# Brainc.net
KiCad netlist of a schematic drawn in EAGLE
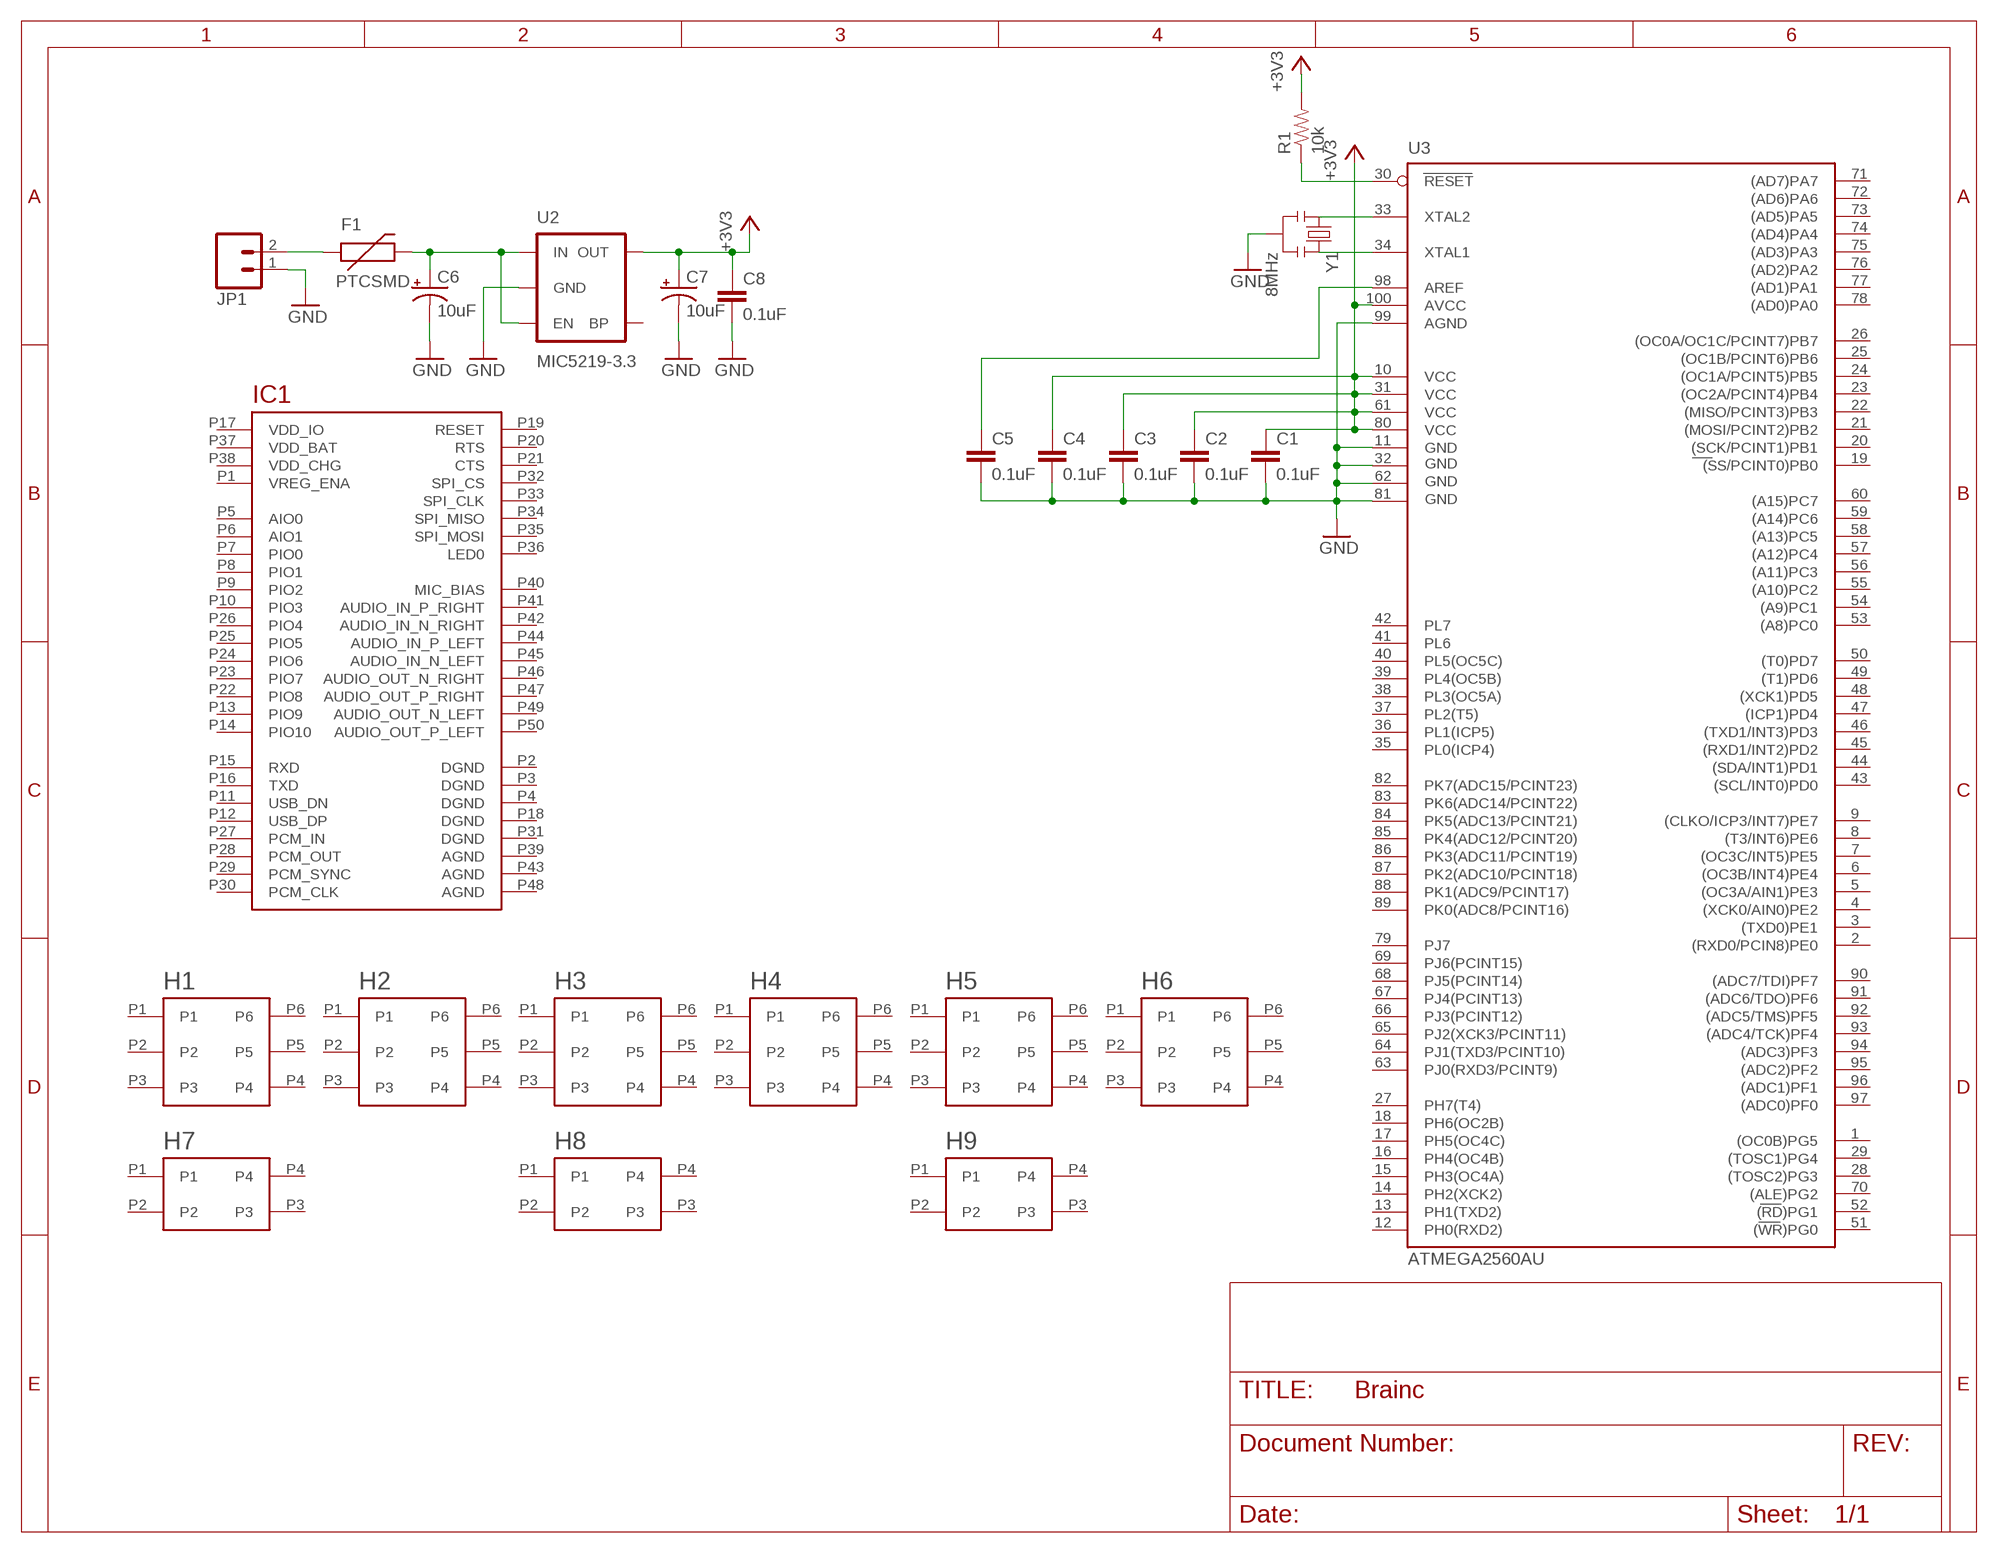
[diagram p0: schematic, sheet 1]

(export (version "E")
  (design (tool "Eeschema 10.0.6"))
  (components
    (comp (ref "C1")
      (value "0.1uF")
      (footprint "eagle-import:0603-CAP")
      (libsource (lib "eagle-import") (part "CAP0603-CAP"))
    )
    (comp (ref "C2")
      (value "0.1uF")
      (footprint "eagle-import:0603-CAP")
      (libsource (lib "eagle-import") (part "CAP0603-CAP"))
    )
    (comp (ref "C3")
      (value "0.1uF")
      (footprint "eagle-import:0603-CAP")
      (libsource (lib "eagle-import") (part "CAP0603-CAP"))
    )
    (comp (ref "C4")
      (value "0.1uF")
      (footprint "eagle-import:0603-CAP")
      (libsource (lib "eagle-import") (part "CAP0603-CAP"))
    )
    (comp (ref "C5")
      (value "0.1uF")
      (footprint "eagle-import:0603-CAP")
      (libsource (lib "eagle-import") (part "CAP0603-CAP"))
    )
    (comp (ref "C6")
      (value "10uF")
      (footprint "eagle-import:EIA3216")
      (libsource (lib "eagle-import") (part "CAP_POL1206"))
    )
    (comp (ref "C7")
      (value "10uF")
      (footprint "eagle-import:EIA3216")
      (libsource (lib "eagle-import") (part "CAP_POL1206"))
    )
    (comp (ref "C8")
      (value "0.1uF")
      (footprint "eagle-import:0603-CAP")
      (libsource (lib "eagle-import") (part "CAP0603-CAP"))
    )
    (comp (ref "F1")
      (value "PTCSMD")
      (footprint "eagle-import:PTC-1206")
      (libsource (lib "eagle-import") (part "PTCSMD"))
    )
    (comp (ref "H1")
      (value "3X2F_1MM_SMD")
      (footprint "eagle-import:3X2F_1MM_SMD")
      (libsource (lib "eagle-import") (part "3X2F_1MM_SMD"))
    )
    (comp (ref "H2")
      (value "3X2F_1MM_SMD")
      (footprint "eagle-import:3X2F_1MM_SMD")
      (libsource (lib "eagle-import") (part "3X2F_1MM_SMD"))
    )
    (comp (ref "H3")
      (value "3X2F_1MM_SMD")
      (footprint "eagle-import:3X2F_1MM_SMD")
      (libsource (lib "eagle-import") (part "3X2F_1MM_SMD"))
    )
    (comp (ref "H4")
      (value "3X2F_1MM_SMD")
      (footprint "eagle-import:3X2F_1MM_SMD")
      (libsource (lib "eagle-import") (part "3X2F_1MM_SMD"))
    )
    (comp (ref "H5")
      (value "3X2F_1MM_SMD")
      (footprint "eagle-import:3X2F_1MM_SMD")
      (libsource (lib "eagle-import") (part "3X2F_1MM_SMD"))
    )
    (comp (ref "H6")
      (value "3X2F_1MM_SMD")
      (footprint "eagle-import:3X2F_1MM_SMD")
      (libsource (lib "eagle-import") (part "3X2F_1MM_SMD"))
    )
    (comp (ref "H7")
      (value "2X2F_1MM_SMD")
      (footprint "eagle-import:2X2F_1MM_SMD")
      (libsource (lib "eagle-import") (part "2X2F_1MM_SMD"))
    )
    (comp (ref "H8")
      (value "2X2F_1MM_SMD")
      (footprint "eagle-import:2X2F_1MM_SMD")
      (libsource (lib "eagle-import") (part "2X2F_1MM_SMD"))
    )
    (comp (ref "H9")
      (value "2X2F_1MM_SMD")
      (footprint "eagle-import:2X2F_1MM_SMD")
      (libsource (lib "eagle-import") (part "2X2F_1MM_SMD"))
    )
    (comp (ref "IC1")
      (value "WT32WT32")
      (footprint "eagle-import:WT32")
      (libsource (lib "eagle-import") (part "WT32WT32"))
    )
    (comp (ref "JP1")
      (value "M02-JST-2MM-SMT")
      (footprint "eagle-import:JST-2-SMD")
      (libsource (lib "eagle-import") (part "M02-JST-2MM-SMT"))
    )
    (comp (ref "R1")
      (value "10k")
      (footprint "eagle-import:0603-RES")
      (libsource (lib "eagle-import") (part "RESISTOR0603-RES"))
    )
    (comp (ref "U2")
      (value "MIC5219-3.3")
      (footprint "eagle-import:SOT23-5")
      (libsource (lib "eagle-import") (part "V_REG_MIC5219SMD"))
    )
    (comp (ref "U3")
      (value "ATMEGA2560AU")
      (footprint "eagle-import:TQFP100")
      (libsource (lib "eagle-import") (part "ATMEGA2560AU"))
    )
    (comp (ref "Y1")
      (value "8MHz")
      (footprint "eagle-import:RESONATOR-SMD")
      (libsource (lib "eagle-import") (part "RESONATORSMD"))
    )
  )
  (nets
    (net (code "1") (name "+3V3") (class "Default")
      (node (ref "C1") (pin "1") (pinfunction "1_1") (pintype "passive"))
      (node (ref "C2") (pin "1") (pinfunction "1_1") (pintype "passive"))
      (node (ref "C3") (pin "1") (pinfunction "1_1") (pintype "passive"))
      (node (ref "C4") (pin "1") (pinfunction "1_1") (pintype "passive"))
      (node (ref "C7") (pin "A") (pinfunction "+_A") (pintype "passive"))
      (node (ref "C8") (pin "1") (pinfunction "1_1") (pintype "passive"))
      (node (ref "R1") (pin "2") (pinfunction "2_2") (pintype "passive"))
      (node (ref "U2") (pin "5") (pinfunction "OUT_5") (pintype "passive"))
      (node (ref "U3") (pin "10") (pinfunction "VCC_10") (pintype "power_in"))
      (node (ref "U3") (pin "100") (pinfunction "AVCC_100") (pintype "power_in"))
      (node (ref "U3") (pin "31") (pinfunction "VCC1_31") (pintype "power_in"))
      (node (ref "U3") (pin "61") (pinfunction "VCC2_61") (pintype "power_in"))
      (node (ref "U3") (pin "80") (pinfunction "VCC3_80") (pintype "power_in"))
    )
    (net (code "2") (name "GND") (class "Default")
      (node (ref "C1") (pin "2") (pinfunction "2_2") (pintype "passive"))
      (node (ref "C2") (pin "2") (pinfunction "2_2") (pintype "passive"))
      (node (ref "C3") (pin "2") (pinfunction "2_2") (pintype "passive"))
      (node (ref "C4") (pin "2") (pinfunction "2_2") (pintype "passive"))
      (node (ref "C5") (pin "2") (pinfunction "2_2") (pintype "passive"))
      (node (ref "C6") (pin "C") (pinfunction "-_C") (pintype "passive"))
      (node (ref "C7") (pin "C") (pinfunction "-_C") (pintype "passive"))
      (node (ref "C8") (pin "2") (pinfunction "2_2") (pintype "passive"))
      (node (ref "JP1") (pin "1") (pinfunction "2_1") (pintype "passive"))
      (node (ref "U2") (pin "2") (pinfunction "GND_2") (pintype "input"))
      (node (ref "U3") (pin "11") (pinfunction "GND_11") (pintype "power_in"))
      (node (ref "U3") (pin "32") (pinfunction "GND1_32") (pintype "power_in"))
      (node (ref "U3") (pin "62") (pinfunction "GND2_62") (pintype "power_in"))
      (node (ref "U3") (pin "81") (pinfunction "GND3_81") (pintype "power_in"))
      (node (ref "U3") (pin "99") (pinfunction "AGND_99") (pintype "power_in"))
      (node (ref "Y1") (pin "2") (pinfunction "2_2") (pintype "passive"))
    )
    (net (code "3") (name "Net-(C6-+)") (class "Default")
      (node (ref "C6") (pin "A") (pinfunction "+_A") (pintype "passive"))
      (node (ref "F1") (pin "2") (pinfunction "2_2") (pintype "bidirectional"))
      (node (ref "U2") (pin "1") (pinfunction "IN_1") (pintype "input"))
      (node (ref "U2") (pin "3") (pinfunction "EN_3") (pintype "input"))
    )
    (net (code "4") (name "Net-(JP1-1)") (class "Default")
      (node (ref "F1") (pin "1") (pinfunction "1_1") (pintype "bidirectional"))
      (node (ref "JP1") (pin "2") (pinfunction "1_2") (pintype "passive"))
    )
    (net (code "5") (name "Net-(U3-AREF)") (class "Default")
      (node (ref "C5") (pin "1") (pinfunction "1_1") (pintype "passive"))
      (node (ref "U3") (pin "98") (pinfunction "AREF_98") (pintype "bidirectional"))
    )
    (net (code "6") (name "Net-(U3-RESET)") (class "Default")
      (node (ref "R1") (pin "1") (pinfunction "1_1") (pintype "passive"))
      (node (ref "U3") (pin "30") (pinfunction "RESET_30") (pintype "input"))
    )
    (net (code "7") (name "Net-(U3-XTAL1)") (class "Default")
      (node (ref "U3") (pin "34") (pinfunction "XTAL1_34") (pintype "input"))
      (node (ref "Y1") (pin "3") (pinfunction "3_3") (pintype "passive"))
    )
    (net (code "8") (name "Net-(U3-XTAL2)") (class "Default")
      (node (ref "U3") (pin "33") (pinfunction "XTAL2_33") (pintype "output"))
      (node (ref "Y1") (pin "1") (pinfunction "1_1") (pintype "passive"))
    )
    (net (code "9") (name "unconnected-(H1-PadP1)") (class "Default")
      (node (ref "H1") (pin "P1") (pinfunction "P1_P1") (pintype "bidirectional"))
    )
    (net (code "10") (name "unconnected-(H1-PadP2)") (class "Default")
      (node (ref "H1") (pin "P2") (pinfunction "P2_P2") (pintype "bidirectional"))
    )
    (net (code "11") (name "unconnected-(H1-PadP3)") (class "Default")
      (node (ref "H1") (pin "P3") (pinfunction "P3_P3") (pintype "bidirectional"))
    )
    (net (code "12") (name "unconnected-(H1-PadP4)") (class "Default")
      (node (ref "H1") (pin "P4") (pinfunction "P4_P4") (pintype "bidirectional"))
    )
    (net (code "13") (name "unconnected-(H1-PadP5)") (class "Default")
      (node (ref "H1") (pin "P5") (pinfunction "P5_P5") (pintype "bidirectional"))
    )
    (net (code "14") (name "unconnected-(H1-PadP6)") (class "Default")
      (node (ref "H1") (pin "P6") (pinfunction "P6_P6") (pintype "bidirectional"))
    )
    (net (code "15") (name "unconnected-(H2-PadP1)") (class "Default")
      (node (ref "H2") (pin "P1") (pinfunction "P1_P1") (pintype "bidirectional"))
    )
    (net (code "16") (name "unconnected-(H2-PadP2)") (class "Default")
      (node (ref "H2") (pin "P2") (pinfunction "P2_P2") (pintype "bidirectional"))
    )
    (net (code "17") (name "unconnected-(H2-PadP3)") (class "Default")
      (node (ref "H2") (pin "P3") (pinfunction "P3_P3") (pintype "bidirectional"))
    )
    (net (code "18") (name "unconnected-(H2-PadP4)") (class "Default")
      (node (ref "H2") (pin "P4") (pinfunction "P4_P4") (pintype "bidirectional"))
    )
    (net (code "19") (name "unconnected-(H2-PadP5)") (class "Default")
      (node (ref "H2") (pin "P5") (pinfunction "P5_P5") (pintype "bidirectional"))
    )
    (net (code "20") (name "unconnected-(H2-PadP6)") (class "Default")
      (node (ref "H2") (pin "P6") (pinfunction "P6_P6") (pintype "bidirectional"))
    )
    (net (code "21") (name "unconnected-(H3-PadP1)") (class "Default")
      (node (ref "H3") (pin "P1") (pinfunction "P1_P1") (pintype "bidirectional"))
    )
    (net (code "22") (name "unconnected-(H3-PadP2)") (class "Default")
      (node (ref "H3") (pin "P2") (pinfunction "P2_P2") (pintype "bidirectional"))
    )
    (net (code "23") (name "unconnected-(H3-PadP3)") (class "Default")
      (node (ref "H3") (pin "P3") (pinfunction "P3_P3") (pintype "bidirectional"))
    )
    (net (code "24") (name "unconnected-(H3-PadP4)") (class "Default")
      (node (ref "H3") (pin "P4") (pinfunction "P4_P4") (pintype "bidirectional"))
    )
    (net (code "25") (name "unconnected-(H3-PadP5)") (class "Default")
      (node (ref "H3") (pin "P5") (pinfunction "P5_P5") (pintype "bidirectional"))
    )
    (net (code "26") (name "unconnected-(H3-PadP6)") (class "Default")
      (node (ref "H3") (pin "P6") (pinfunction "P6_P6") (pintype "bidirectional"))
    )
    (net (code "27") (name "unconnected-(H4-PadP1)") (class "Default")
      (node (ref "H4") (pin "P1") (pinfunction "P1_P1") (pintype "bidirectional"))
    )
    (net (code "28") (name "unconnected-(H4-PadP2)") (class "Default")
      (node (ref "H4") (pin "P2") (pinfunction "P2_P2") (pintype "bidirectional"))
    )
    (net (code "29") (name "unconnected-(H4-PadP3)") (class "Default")
      (node (ref "H4") (pin "P3") (pinfunction "P3_P3") (pintype "bidirectional"))
    )
    (net (code "30") (name "unconnected-(H4-PadP4)") (class "Default")
      (node (ref "H4") (pin "P4") (pinfunction "P4_P4") (pintype "bidirectional"))
    )
    (net (code "31") (name "unconnected-(H4-PadP5)") (class "Default")
      (node (ref "H4") (pin "P5") (pinfunction "P5_P5") (pintype "bidirectional"))
    )
    (net (code "32") (name "unconnected-(H4-PadP6)") (class "Default")
      (node (ref "H4") (pin "P6") (pinfunction "P6_P6") (pintype "bidirectional"))
    )
    (net (code "33") (name "unconnected-(H5-PadP1)") (class "Default")
      (node (ref "H5") (pin "P1") (pinfunction "P1_P1") (pintype "bidirectional"))
    )
    (net (code "34") (name "unconnected-(H5-PadP2)") (class "Default")
      (node (ref "H5") (pin "P2") (pinfunction "P2_P2") (pintype "bidirectional"))
    )
    (net (code "35") (name "unconnected-(H5-PadP3)") (class "Default")
      (node (ref "H5") (pin "P3") (pinfunction "P3_P3") (pintype "bidirectional"))
    )
    (net (code "36") (name "unconnected-(H5-PadP4)") (class "Default")
      (node (ref "H5") (pin "P4") (pinfunction "P4_P4") (pintype "bidirectional"))
    )
    (net (code "37") (name "unconnected-(H5-PadP5)") (class "Default")
      (node (ref "H5") (pin "P5") (pinfunction "P5_P5") (pintype "bidirectional"))
    )
    (net (code "38") (name "unconnected-(H5-PadP6)") (class "Default")
      (node (ref "H5") (pin "P6") (pinfunction "P6_P6") (pintype "bidirectional"))
    )
    (net (code "39") (name "unconnected-(H6-PadP1)") (class "Default")
      (node (ref "H6") (pin "P1") (pinfunction "P1_P1") (pintype "bidirectional"))
    )
    (net (code "40") (name "unconnected-(H6-PadP2)") (class "Default")
      (node (ref "H6") (pin "P2") (pinfunction "P2_P2") (pintype "bidirectional"))
    )
    (net (code "41") (name "unconnected-(H6-PadP3)") (class "Default")
      (node (ref "H6") (pin "P3") (pinfunction "P3_P3") (pintype "bidirectional"))
    )
    (net (code "42") (name "unconnected-(H6-PadP4)") (class "Default")
      (node (ref "H6") (pin "P4") (pinfunction "P4_P4") (pintype "bidirectional"))
    )
    (net (code "43") (name "unconnected-(H6-PadP5)") (class "Default")
      (node (ref "H6") (pin "P5") (pinfunction "P5_P5") (pintype "bidirectional"))
    )
    (net (code "44") (name "unconnected-(H6-PadP6)") (class "Default")
      (node (ref "H6") (pin "P6") (pinfunction "P6_P6") (pintype "bidirectional"))
    )
    (net (code "45") (name "unconnected-(H7-PadP1)") (class "Default")
      (node (ref "H7") (pin "P1") (pinfunction "P1_P1") (pintype "bidirectional"))
    )
    (net (code "46") (name "unconnected-(H7-PadP2)") (class "Default")
      (node (ref "H7") (pin "P2") (pinfunction "P2_P2") (pintype "bidirectional"))
    )
    (net (code "47") (name "unconnected-(H7-PadP3)") (class "Default")
      (node (ref "H7") (pin "P3") (pinfunction "P3_P3") (pintype "bidirectional"))
    )
    (net (code "48") (name "unconnected-(H7-PadP4)") (class "Default")
      (node (ref "H7") (pin "P4") (pinfunction "P4_P4") (pintype "bidirectional"))
    )
    (net (code "49") (name "unconnected-(H8-PadP1)") (class "Default")
      (node (ref "H8") (pin "P1") (pinfunction "P1_P1") (pintype "bidirectional"))
    )
    (net (code "50") (name "unconnected-(H8-PadP2)") (class "Default")
      (node (ref "H8") (pin "P2") (pinfunction "P2_P2") (pintype "bidirectional"))
    )
    (net (code "51") (name "unconnected-(H8-PadP3)") (class "Default")
      (node (ref "H8") (pin "P3") (pinfunction "P3_P3") (pintype "bidirectional"))
    )
    (net (code "52") (name "unconnected-(H8-PadP4)") (class "Default")
      (node (ref "H8") (pin "P4") (pinfunction "P4_P4") (pintype "bidirectional"))
    )
    (net (code "53") (name "unconnected-(H9-PadP1)") (class "Default")
      (node (ref "H9") (pin "P1") (pinfunction "P1_P1") (pintype "bidirectional"))
    )
    (net (code "54") (name "unconnected-(H9-PadP2)") (class "Default")
      (node (ref "H9") (pin "P2") (pinfunction "P2_P2") (pintype "bidirectional"))
    )
    (net (code "55") (name "unconnected-(H9-PadP3)") (class "Default")
      (node (ref "H9") (pin "P3") (pinfunction "P3_P3") (pintype "bidirectional"))
    )
    (net (code "56") (name "unconnected-(H9-PadP4)") (class "Default")
      (node (ref "H9") (pin "P4") (pinfunction "P4_P4") (pintype "bidirectional"))
    )
    (net (code "57") (name "unconnected-(IC1-AGND-PadP39)") (class "Default")
      (node (ref "IC1") (pin "P39") (pinfunction "AGND_P39") (pintype "bidirectional"))
    )
    (net (code "58") (name "unconnected-(IC1-AGND-PadP43)") (class "Default")
      (node (ref "IC1") (pin "P43") (pinfunction "AGND_P43") (pintype "bidirectional"))
    )
    (net (code "59") (name "unconnected-(IC1-AGND-PadP48)") (class "Default")
      (node (ref "IC1") (pin "P48") (pinfunction "AGND_P48") (pintype "bidirectional"))
    )
    (net (code "60") (name "unconnected-(IC1-AIO0-PadP5)") (class "Default")
      (node (ref "IC1") (pin "P5") (pinfunction "AIO0_P5") (pintype "bidirectional"))
    )
    (net (code "61") (name "unconnected-(IC1-AIO1-PadP6)") (class "Default")
      (node (ref "IC1") (pin "P6") (pinfunction "AIO1_P6") (pintype "bidirectional"))
    )
    (net (code "62") (name "unconnected-(IC1-AUDIO_IN_N_LEFT-PadP45)") (class "Default")
      (node (ref "IC1") (pin "P45") (pinfunction "AUDIO_IN_N_LEFT_P45") (pintype "bidirectional"))
    )
    (net (code "63") (name "unconnected-(IC1-AUDIO_IN_N_RIGHT-PadP42)") (class "Default")
      (node (ref "IC1") (pin "P42") (pinfunction "AUDIO_IN_N_RIGHT_P42") (pintype "bidirectional"))
    )
    (net (code "64") (name "unconnected-(IC1-AUDIO_IN_P_LEFT-PadP44)") (class "Default")
      (node (ref "IC1") (pin "P44") (pinfunction "AUDIO_IN_P_LEFT_P44") (pintype "bidirectional"))
    )
    (net (code "65") (name "unconnected-(IC1-AUDIO_IN_P_RIGHT-PadP41)") (class "Default")
      (node (ref "IC1") (pin "P41") (pinfunction "AUDIO_IN_P_RIGHT_P41") (pintype "bidirectional"))
    )
    (net (code "66") (name "unconnected-(IC1-AUDIO_OUT_N_LEFT-PadP49)") (class "Default")
      (node (ref "IC1") (pin "P49") (pinfunction "AUDIO_OUT_N_LEFT_P49") (pintype "bidirectional"))
    )
    (net (code "67") (name "unconnected-(IC1-AUDIO_OUT_N_RIGHT-PadP46)") (class "Default")
      (node (ref "IC1") (pin "P46") (pinfunction "AUDIO_OUT_N_RIGHT_P46") (pintype "bidirectional"))
    )
    (net (code "68") (name "unconnected-(IC1-AUDIO_OUT_P_LEFT-PadP50)") (class "Default")
      (node (ref "IC1") (pin "P50") (pinfunction "AUDIO_OUT_P_LEFT_P50") (pintype "bidirectional"))
    )
    (net (code "69") (name "unconnected-(IC1-AUDIO_OUT_P_RIGHT-PadP47)") (class "Default")
      (node (ref "IC1") (pin "P47") (pinfunction "AUDIO_OUT_P_RIGHT_P47") (pintype "bidirectional"))
    )
    (net (code "70") (name "unconnected-(IC1-CTS-PadP21)") (class "Default")
      (node (ref "IC1") (pin "P21") (pinfunction "CTS_P21") (pintype "bidirectional"))
    )
    (net (code "71") (name "unconnected-(IC1-DGND-PadP2)") (class "Default")
      (node (ref "IC1") (pin "P2") (pinfunction "DGND_P2") (pintype "bidirectional"))
    )
    (net (code "72") (name "unconnected-(IC1-DGND-PadP3)") (class "Default")
      (node (ref "IC1") (pin "P3") (pinfunction "DGND_P3") (pintype "bidirectional"))
    )
    (net (code "73") (name "unconnected-(IC1-DGND-PadP4)") (class "Default")
      (node (ref "IC1") (pin "P4") (pinfunction "DGND_P4") (pintype "bidirectional"))
    )
    (net (code "74") (name "unconnected-(IC1-DGND-PadP18)") (class "Default")
      (node (ref "IC1") (pin "P18") (pinfunction "DGND_P18") (pintype "bidirectional"))
    )
    (net (code "75") (name "unconnected-(IC1-DGND-PadP31)") (class "Default")
      (node (ref "IC1") (pin "P31") (pinfunction "DGND_P31") (pintype "bidirectional"))
    )
    (net (code "76") (name "unconnected-(IC1-LED0-PadP36)") (class "Default")
      (node (ref "IC1") (pin "P36") (pinfunction "LED0_P36") (pintype "bidirectional"))
    )
    (net (code "77") (name "unconnected-(IC1-MIC_BIAS-PadP40)") (class "Default")
      (node (ref "IC1") (pin "P40") (pinfunction "MIC_BIAS_P40") (pintype "bidirectional"))
    )
    (net (code "78") (name "unconnected-(IC1-PCM_CLK-PadP30)") (class "Default")
      (node (ref "IC1") (pin "P30") (pinfunction "PCM_CLK_P30") (pintype "bidirectional"))
    )
    (net (code "79") (name "unconnected-(IC1-PCM_IN-PadP27)") (class "Default")
      (node (ref "IC1") (pin "P27") (pinfunction "PCM_IN_P27") (pintype "bidirectional"))
    )
    (net (code "80") (name "unconnected-(IC1-PCM_OUT-PadP28)") (class "Default")
      (node (ref "IC1") (pin "P28") (pinfunction "PCM_OUT_P28") (pintype "bidirectional"))
    )
    (net (code "81") (name "unconnected-(IC1-PCM_SYNC-PadP29)") (class "Default")
      (node (ref "IC1") (pin "P29") (pinfunction "PCM_SYNC_P29") (pintype "bidirectional"))
    )
    (net (code "82") (name "unconnected-(IC1-PIO0-PadP7)") (class "Default")
      (node (ref "IC1") (pin "P7") (pinfunction "PIO0_P7") (pintype "bidirectional"))
    )
    (net (code "83") (name "unconnected-(IC1-PIO1-PadP8)") (class "Default")
      (node (ref "IC1") (pin "P8") (pinfunction "PIO1_P8") (pintype "bidirectional"))
    )
    (net (code "84") (name "unconnected-(IC1-PIO2-PadP9)") (class "Default")
      (node (ref "IC1") (pin "P9") (pinfunction "PIO2_P9") (pintype "bidirectional"))
    )
    (net (code "85") (name "unconnected-(IC1-PIO3-PadP10)") (class "Default")
      (node (ref "IC1") (pin "P10") (pinfunction "PIO3_P10") (pintype "bidirectional"))
    )
    (net (code "86") (name "unconnected-(IC1-PIO4-PadP26)") (class "Default")
      (node (ref "IC1") (pin "P26") (pinfunction "PIO4_P26") (pintype "bidirectional"))
    )
    (net (code "87") (name "unconnected-(IC1-PIO5-PadP25)") (class "Default")
      (node (ref "IC1") (pin "P25") (pinfunction "PIO5_P25") (pintype "bidirectional"))
    )
    (net (code "88") (name "unconnected-(IC1-PIO6-PadP24)") (class "Default")
      (node (ref "IC1") (pin "P24") (pinfunction "PIO6_P24") (pintype "bidirectional"))
    )
    (net (code "89") (name "unconnected-(IC1-PIO7-PadP23)") (class "Default")
      (node (ref "IC1") (pin "P23") (pinfunction "PIO7_P23") (pintype "bidirectional"))
    )
    (net (code "90") (name "unconnected-(IC1-PIO8-PadP22)") (class "Default")
      (node (ref "IC1") (pin "P22") (pinfunction "PIO8_P22") (pintype "bidirectional"))
    )
    (net (code "91") (name "unconnected-(IC1-PIO9-PadP13)") (class "Default")
      (node (ref "IC1") (pin "P13") (pinfunction "PIO9_P13") (pintype "bidirectional"))
    )
    (net (code "92") (name "unconnected-(IC1-PIO10-PadP14)") (class "Default")
      (node (ref "IC1") (pin "P14") (pinfunction "PIO10_P14") (pintype "bidirectional"))
    )
    (net (code "93") (name "unconnected-(IC1-RESET-PadP19)") (class "Default")
      (node (ref "IC1") (pin "P19") (pinfunction "RESET_P19") (pintype "bidirectional"))
    )
    (net (code "94") (name "unconnected-(IC1-RTS-PadP20)") (class "Default")
      (node (ref "IC1") (pin "P20") (pinfunction "RTS_P20") (pintype "bidirectional"))
    )
    (net (code "95") (name "unconnected-(IC1-RXD-PadP15)") (class "Default")
      (node (ref "IC1") (pin "P15") (pinfunction "RXD_P15") (pintype "bidirectional"))
    )
    (net (code "96") (name "unconnected-(IC1-SPI_CLK-PadP33)") (class "Default")
      (node (ref "IC1") (pin "P33") (pinfunction "SPI_CLK_P33") (pintype "bidirectional"))
    )
    (net (code "97") (name "unconnected-(IC1-SPI_CS-PadP32)") (class "Default")
      (node (ref "IC1") (pin "P32") (pinfunction "SPI_CS_P32") (pintype "bidirectional"))
    )
    (net (code "98") (name "unconnected-(IC1-SPI_MISO-PadP34)") (class "Default")
      (node (ref "IC1") (pin "P34") (pinfunction "SPI_MISO_P34") (pintype "bidirectional"))
    )
    (net (code "99") (name "unconnected-(IC1-SPI_MOSI-PadP35)") (class "Default")
      (node (ref "IC1") (pin "P35") (pinfunction "SPI_MOSI_P35") (pintype "bidirectional"))
    )
    (net (code "100") (name "unconnected-(IC1-TXD-PadP16)") (class "Default")
      (node (ref "IC1") (pin "P16") (pinfunction "TXD_P16") (pintype "bidirectional"))
    )
    (net (code "101") (name "unconnected-(IC1-USB_DN-PadP11)") (class "Default")
      (node (ref "IC1") (pin "P11") (pinfunction "USB_DN_P11") (pintype "bidirectional"))
    )
    (net (code "102") (name "unconnected-(IC1-USB_DP-PadP12)") (class "Default")
      (node (ref "IC1") (pin "P12") (pinfunction "USB_DP_P12") (pintype "bidirectional"))
    )
    (net (code "103") (name "unconnected-(IC1-VDD_BAT-PadP37)") (class "Default")
      (node (ref "IC1") (pin "P37") (pinfunction "VDD_BAT_P37") (pintype "bidirectional"))
    )
    (net (code "104") (name "unconnected-(IC1-VDD_CHG-PadP38)") (class "Default")
      (node (ref "IC1") (pin "P38") (pinfunction "VDD_CHG_P38") (pintype "bidirectional"))
    )
    (net (code "105") (name "unconnected-(IC1-VDD_IO-PadP17)") (class "Default")
      (node (ref "IC1") (pin "P17") (pinfunction "VDD_IO_P17") (pintype "bidirectional"))
    )
    (net (code "106") (name "unconnected-(IC1-VREG_ENA-PadP1)") (class "Default")
      (node (ref "IC1") (pin "P1") (pinfunction "VREG_ENA_P1") (pintype "bidirectional"))
    )
    (net (code "107") (name "unconnected-(U2-BP-Pad4)") (class "Default")
      (node (ref "U2") (pin "4") (pinfunction "BP_4") (pintype "input"))
    )
    (net (code "108") (name "unconnected-(U3-(A8)PC0-Pad53)") (class "Default")
      (node (ref "U3") (pin "53") (pinfunction "(A8)PC0_53") (pintype "bidirectional"))
    )
    (net (code "109") (name "unconnected-(U3-(A9)PC1-Pad54)") (class "Default")
      (node (ref "U3") (pin "54") (pinfunction "(A9)PC1_54") (pintype "bidirectional"))
    )
    (net (code "110") (name "unconnected-(U3-(A10)PC2-Pad55)") (class "Default")
      (node (ref "U3") (pin "55") (pinfunction "(A10)PC2_55") (pintype "bidirectional"))
    )
    (net (code "111") (name "unconnected-(U3-(A11)PC3-Pad56)") (class "Default")
      (node (ref "U3") (pin "56") (pinfunction "(A11)PC3_56") (pintype "bidirectional"))
    )
    (net (code "112") (name "unconnected-(U3-(A12)PC4-Pad57)") (class "Default")
      (node (ref "U3") (pin "57") (pinfunction "(A12)PC4_57") (pintype "bidirectional"))
    )
    (net (code "113") (name "unconnected-(U3-(A13)PC5-Pad58)") (class "Default")
      (node (ref "U3") (pin "58") (pinfunction "(A13)PC5_58") (pintype "bidirectional"))
    )
    (net (code "114") (name "unconnected-(U3-(A14)PC6-Pad59)") (class "Default")
      (node (ref "U3") (pin "59") (pinfunction "(A14)PC6_59") (pintype "bidirectional"))
    )
    (net (code "115") (name "unconnected-(U3-(A15)PC7-Pad60)") (class "Default")
      (node (ref "U3") (pin "60") (pinfunction "(A15)PC7_60") (pintype "bidirectional"))
    )
    (net (code "116") (name "unconnected-(U3-(AD0)PA0-Pad78)") (class "Default")
      (node (ref "U3") (pin "78") (pinfunction "(AD0)PA0_78") (pintype "bidirectional"))
    )
    (net (code "117") (name "unconnected-(U3-(AD1)PA1-Pad77)") (class "Default")
      (node (ref "U3") (pin "77") (pinfunction "(AD1)PA1_77") (pintype "bidirectional"))
    )
    (net (code "118") (name "unconnected-(U3-(AD2)PA2-Pad76)") (class "Default")
      (node (ref "U3") (pin "76") (pinfunction "(AD2)PA2_76") (pintype "bidirectional"))
    )
    (net (code "119") (name "unconnected-(U3-(AD3)PA3-Pad75)") (class "Default")
      (node (ref "U3") (pin "75") (pinfunction "(AD3)PA3_75") (pintype "bidirectional"))
    )
    (net (code "120") (name "unconnected-(U3-(AD4)PA4-Pad74)") (class "Default")
      (node (ref "U3") (pin "74") (pinfunction "(AD4)PA4_74") (pintype "bidirectional"))
    )
    (net (code "121") (name "unconnected-(U3-(AD5)PA5-Pad73)") (class "Default")
      (node (ref "U3") (pin "73") (pinfunction "(AD5)PA5_73") (pintype "bidirectional"))
    )
    (net (code "122") (name "unconnected-(U3-(AD6)PA6-Pad72)") (class "Default")
      (node (ref "U3") (pin "72") (pinfunction "(AD6)PA6_72") (pintype "bidirectional"))
    )
    (net (code "123") (name "unconnected-(U3-(AD7)PA7-Pad71)") (class "Default")
      (node (ref "U3") (pin "71") (pinfunction "(AD7)PA7_71") (pintype "bidirectional"))
    )
    (net (code "124") (name "unconnected-(U3-(ADC0)PF0-Pad97)") (class "Default")
      (node (ref "U3") (pin "97") (pinfunction "(ADC0)PF0_97") (pintype "bidirectional"))
    )
    (net (code "125") (name "unconnected-(U3-(ADC1)PF1-Pad96)") (class "Default")
      (node (ref "U3") (pin "96") (pinfunction "(ADC1)PF1_96") (pintype "bidirectional"))
    )
    (net (code "126") (name "unconnected-(U3-(ADC2)PF2-Pad95)") (class "Default")
      (node (ref "U3") (pin "95") (pinfunction "(ADC2)PF2_95") (pintype "bidirectional"))
    )
    (net (code "127") (name "unconnected-(U3-(ADC3)PF3-Pad94)") (class "Default")
      (node (ref "U3") (pin "94") (pinfunction "(ADC3)PF3_94") (pintype "bidirectional"))
    )
    (net (code "128") (name "unconnected-(U3-(ADC4{slash}TCK)PF4-Pad93)") (class "Default")
      (node (ref "U3") (pin "93") (pinfunction "(ADC4/TCK)PF4_93") (pintype "bidirectional"))
    )
    (net (code "129") (name "unconnected-(U3-(ADC5{slash}TMS)PF5-Pad92)") (class "Default")
      (node (ref "U3") (pin "92") (pinfunction "(ADC5/TMS)PF5_92") (pintype "bidirectional"))
    )
    (net (code "130") (name "unconnected-(U3-(ADC6{slash}TDO)PF6-Pad91)") (class "Default")
      (node (ref "U3") (pin "91") (pinfunction "(ADC6/TDO)PF6_91") (pintype "bidirectional"))
    )
    (net (code "131") (name "unconnected-(U3-(ADC7{slash}TDI)PF7-Pad90)") (class "Default")
      (node (ref "U3") (pin "90") (pinfunction "(ADC7/TDI)PF7_90") (pintype "bidirectional"))
    )
    (net (code "132") (name "unconnected-(U3-(ALE)PG2-Pad70)") (class "Default")
      (node (ref "U3") (pin "70") (pinfunction "(ALE)PG2_70") (pintype "bidirectional"))
    )
    (net (code "133") (name "unconnected-(U3-(CLKO{slash}ICP3{slash}INT7)PE7-Pad9)") (class "Default")
      (node (ref "U3") (pin "9") (pinfunction "(CLKO/ICP3/INT7)PE7_9") (pintype "bidirectional"))
    )
    (net (code "134") (name "unconnected-(U3-(ICP1)PD4-Pad47)") (class "Default")
      (node (ref "U3") (pin "47") (pinfunction "(ICP1)PD4_47") (pintype "bidirectional"))
    )
    (net (code "135") (name "unconnected-(U3-(MISO{slash}PCINT3)PB3-Pad22)") (class "Default")
      (node (ref "U3") (pin "22") (pinfunction "(MISO/PCINT3)PB3_22") (pintype "bidirectional"))
    )
    (net (code "136") (name "unconnected-(U3-(MOSI{slash}PCINT2)PB2-Pad21)") (class "Default")
      (node (ref "U3") (pin "21") (pinfunction "(MOSI/PCINT2)PB2_21") (pintype "bidirectional"))
    )
    (net (code "137") (name "unconnected-(U3-(OC0A{slash}OC1C{slash}PCINT7)PB7-Pad26)") (class "Default")
      (node (ref "U3") (pin "26") (pinfunction "(OC0A/OC1C/PCINT7)PB7_26") (pintype "bidirectional"))
    )
    (net (code "138") (name "unconnected-(U3-(OC0B)PG5-Pad1)") (class "Default")
      (node (ref "U3") (pin "1") (pinfunction "(OC0B)PG5_1") (pintype "bidirectional"))
    )
    (net (code "139") (name "unconnected-(U3-(OC1A{slash}PCINT5)PB5-Pad24)") (class "Default")
      (node (ref "U3") (pin "24") (pinfunction "(OC1A/PCINT5)PB5_24") (pintype "bidirectional"))
    )
    (net (code "140") (name "unconnected-(U3-(OC1B{slash}PCINT6)PB6-Pad25)") (class "Default")
      (node (ref "U3") (pin "25") (pinfunction "(OC1B/PCINT6)PB6_25") (pintype "bidirectional"))
    )
    (net (code "141") (name "unconnected-(U3-(OC2A{slash}PCINT4)PB4-Pad23)") (class "Default")
      (node (ref "U3") (pin "23") (pinfunction "(OC2A/PCINT4)PB4_23") (pintype "bidirectional"))
    )
    (net (code "142") (name "unconnected-(U3-(OC3A{slash}AIN1)PE3-Pad5)") (class "Default")
      (node (ref "U3") (pin "5") (pinfunction "(OC3A/AIN1)PE3_5") (pintype "bidirectional"))
    )
    (net (code "143") (name "unconnected-(U3-(OC3B{slash}INT4)PE4-Pad6)") (class "Default")
      (node (ref "U3") (pin "6") (pinfunction "(OC3B/INT4)PE4_6") (pintype "bidirectional"))
    )
    (net (code "144") (name "unconnected-(U3-(OC3C{slash}INT5)PE5-Pad7)") (class "Default")
      (node (ref "U3") (pin "7") (pinfunction "(OC3C/INT5)PE5_7") (pintype "bidirectional"))
    )
    (net (code "145") (name "unconnected-(U3-(RD)PG1-Pad52)") (class "Default")
      (node (ref "U3") (pin "52") (pinfunction "(RD)PG1_52") (pintype "bidirectional"))
    )
    (net (code "146") (name "unconnected-(U3-(RXD0{slash}PCIN8)PE0-Pad2)") (class "Default")
      (node (ref "U3") (pin "2") (pinfunction "(RXD0/PCIN8)PE0_2") (pintype "bidirectional"))
    )
    (net (code "147") (name "unconnected-(U3-(RXD1{slash}INT2)PD2-Pad45)") (class "Default")
      (node (ref "U3") (pin "45") (pinfunction "(RXD1/INT2)PD2_45") (pintype "bidirectional"))
    )
    (net (code "148") (name "unconnected-(U3-(SCK{slash}PCINT1)PB1-Pad20)") (class "Default")
      (node (ref "U3") (pin "20") (pinfunction "(SCK/PCINT1)PB1_20") (pintype "bidirectional"))
    )
    (net (code "149") (name "unconnected-(U3-(SCL{slash}INT0)PD0-Pad43)") (class "Default")
      (node (ref "U3") (pin "43") (pinfunction "(SCL/INT0)PD0_43") (pintype "bidirectional"))
    )
    (net (code "150") (name "unconnected-(U3-(SDA{slash}INT1)PD1-Pad44)") (class "Default")
      (node (ref "U3") (pin "44") (pinfunction "(SDA/INT1)PD1_44") (pintype "bidirectional"))
    )
    (net (code "151") (name "unconnected-(U3-(SS{slash}PCINT0)PB0-Pad19)") (class "Default")
      (node (ref "U3") (pin "19") (pinfunction "(SS/PCINT0)PB0_19") (pintype "bidirectional"))
    )
    (net (code "152") (name "unconnected-(U3-(T0)PD7-Pad50)") (class "Default")
      (node (ref "U3") (pin "50") (pinfunction "(T0)PD7_50") (pintype "bidirectional"))
    )
    (net (code "153") (name "unconnected-(U3-(T1)PD6-Pad49)") (class "Default")
      (node (ref "U3") (pin "49") (pinfunction "(T1)PD6_49") (pintype "bidirectional"))
    )
    (net (code "154") (name "unconnected-(U3-(T3{slash}INT6)PE6-Pad8)") (class "Default")
      (node (ref "U3") (pin "8") (pinfunction "(T3/INT6)PE6_8") (pintype "bidirectional"))
    )
    (net (code "155") (name "unconnected-(U3-(TOSC1)PG4-Pad29)") (class "Default")
      (node (ref "U3") (pin "29") (pinfunction "(TOSC1)PG4_29") (pintype "bidirectional"))
    )
    (net (code "156") (name "unconnected-(U3-(TOSC2)PG3-Pad28)") (class "Default")
      (node (ref "U3") (pin "28") (pinfunction "(TOSC2)PG3_28") (pintype "bidirectional"))
    )
    (net (code "157") (name "unconnected-(U3-(TXD0)PE1-Pad3)") (class "Default")
      (node (ref "U3") (pin "3") (pinfunction "(TXD0)PE1_3") (pintype "bidirectional"))
    )
    (net (code "158") (name "unconnected-(U3-(TXD1{slash}INT3)PD3-Pad46)") (class "Default")
      (node (ref "U3") (pin "46") (pinfunction "(TXD1/INT3)PD3_46") (pintype "bidirectional"))
    )
    (net (code "159") (name "unconnected-(U3-(WR)PG0-Pad51)") (class "Default")
      (node (ref "U3") (pin "51") (pinfunction "(WR)PG0_51") (pintype "bidirectional"))
    )
    (net (code "160") (name "unconnected-(U3-(XCK0{slash}AIN0)PE2-Pad4)") (class "Default")
      (node (ref "U3") (pin "4") (pinfunction "(XCK0/AIN0)PE2_4") (pintype "bidirectional"))
    )
    (net (code "161") (name "unconnected-(U3-(XCK1)PD5-Pad48)") (class "Default")
      (node (ref "U3") (pin "48") (pinfunction "(XCK1)PD5_48") (pintype "bidirectional"))
    )
    (net (code "162") (name "unconnected-(U3-PH0(RXD2)-Pad12)") (class "Default")
      (node (ref "U3") (pin "12") (pinfunction "PH0(RXD2)_12") (pintype "bidirectional"))
    )
    (net (code "163") (name "unconnected-(U3-PH1(TXD2)-Pad13)") (class "Default")
      (node (ref "U3") (pin "13") (pinfunction "PH1(TXD2)_13") (pintype "bidirectional"))
    )
    (net (code "164") (name "unconnected-(U3-PH2(XCK2)-Pad14)") (class "Default")
      (node (ref "U3") (pin "14") (pinfunction "PH2(XCK2)_14") (pintype "bidirectional"))
    )
    (net (code "165") (name "unconnected-(U3-PH3(OC4A)-Pad15)") (class "Default")
      (node (ref "U3") (pin "15") (pinfunction "PH3(OC4A)_15") (pintype "bidirectional"))
    )
    (net (code "166") (name "unconnected-(U3-PH4(OC4B)-Pad16)") (class "Default")
      (node (ref "U3") (pin "16") (pinfunction "PH4(OC4B)_16") (pintype "bidirectional"))
    )
    (net (code "167") (name "unconnected-(U3-PH5(OC4C)-Pad17)") (class "Default")
      (node (ref "U3") (pin "17") (pinfunction "PH5(OC4C)_17") (pintype "bidirectional"))
    )
    (net (code "168") (name "unconnected-(U3-PH6(OC2B)-Pad18)") (class "Default")
      (node (ref "U3") (pin "18") (pinfunction "PH6(OC2B)_18") (pintype "bidirectional"))
    )
    (net (code "169") (name "unconnected-(U3-PH7(T4)-Pad27)") (class "Default")
      (node (ref "U3") (pin "27") (pinfunction "PH7(T4)_27") (pintype "bidirectional"))
    )
    (net (code "170") (name "unconnected-(U3-PJ0(RXD3{slash}PCINT9)-Pad63)") (class "Default")
      (node (ref "U3") (pin "63") (pinfunction "PJ0(RXD3/PCINT9)_63") (pintype "bidirectional"))
    )
    (net (code "171") (name "unconnected-(U3-PJ1(TXD3{slash}PCINT10)-Pad64)") (class "Default")
      (node (ref "U3") (pin "64") (pinfunction "PJ1(TXD3/PCINT10)_64") (pintype "bidirectional"))
    )
    (net (code "172") (name "unconnected-(U3-PJ2(XCK3{slash}PCINT11)-Pad65)") (class "Default")
      (node (ref "U3") (pin "65") (pinfunction "PJ2(XCK3/PCINT11)_65") (pintype "bidirectional"))
    )
    (net (code "173") (name "unconnected-(U3-PJ3(PCINT12)-Pad66)") (class "Default")
      (node (ref "U3") (pin "66") (pinfunction "PJ3(PCINT12)_66") (pintype "bidirectional"))
    )
    (net (code "174") (name "unconnected-(U3-PJ4(PCINT13)-Pad67)") (class "Default")
      (node (ref "U3") (pin "67") (pinfunction "PJ4(PCINT13)_67") (pintype "bidirectional"))
    )
    (net (code "175") (name "unconnected-(U3-PJ5(PCINT14)-Pad68)") (class "Default")
      (node (ref "U3") (pin "68") (pinfunction "PJ5(PCINT14)_68") (pintype "bidirectional"))
    )
    (net (code "176") (name "unconnected-(U3-PJ6(PCINT15)-Pad69)") (class "Default")
      (node (ref "U3") (pin "69") (pinfunction "PJ6(PCINT15)_69") (pintype "bidirectional"))
    )
    (net (code "177") (name "unconnected-(U3-PJ7-Pad79)") (class "Default")
      (node (ref "U3") (pin "79") (pinfunction "PJ7_79") (pintype "bidirectional"))
    )
    (net (code "178") (name "unconnected-(U3-PK0(ADC8{slash}PCINT16)-Pad89)") (class "Default")
      (node (ref "U3") (pin "89") (pinfunction "PK0(ADC8/PCINT16)_89") (pintype "bidirectional"))
    )
    (net (code "179") (name "unconnected-(U3-PK1(ADC9{slash}PCINT17)-Pad88)") (class "Default")
      (node (ref "U3") (pin "88") (pinfunction "PK1(ADC9/PCINT17)_88") (pintype "bidirectional"))
    )
    (net (code "180") (name "unconnected-(U3-PK2(ADC10{slash}PCINT18)-Pad87)") (class "Default")
      (node (ref "U3") (pin "87") (pinfunction "PK2(ADC10/PCINT18)_87") (pintype "bidirectional"))
    )
    (net (code "181") (name "unconnected-(U3-PK3(ADC11{slash}PCINT19)-Pad86)") (class "Default")
      (node (ref "U3") (pin "86") (pinfunction "PK3(ADC11/PCINT19)_86") (pintype "bidirectional"))
    )
    (net (code "182") (name "unconnected-(U3-PK4(ADC12{slash}PCINT20)-Pad85)") (class "Default")
      (node (ref "U3") (pin "85") (pinfunction "PK4(ADC12/PCINT20)_85") (pintype "bidirectional"))
    )
    (net (code "183") (name "unconnected-(U3-PK5(ADC13{slash}PCINT21)-Pad84)") (class "Default")
      (node (ref "U3") (pin "84") (pinfunction "PK5(ADC13/PCINT21)_84") (pintype "bidirectional"))
    )
    (net (code "184") (name "unconnected-(U3-PK6(ADC14{slash}PCINT22)-Pad83)") (class "Default")
      (node (ref "U3") (pin "83") (pinfunction "PK6(ADC14/PCINT22)_83") (pintype "bidirectional"))
    )
    (net (code "185") (name "unconnected-(U3-PK7(ADC15{slash}PCINT23)-Pad82)") (class "Default")
      (node (ref "U3") (pin "82") (pinfunction "PK7(ADC15/PCINT23)_82") (pintype "bidirectional"))
    )
    (net (code "186") (name "unconnected-(U3-PL0(ICP4)-Pad35)") (class "Default")
      (node (ref "U3") (pin "35") (pinfunction "PL0(ICP4)_35") (pintype "bidirectional"))
    )
    (net (code "187") (name "unconnected-(U3-PL1(ICP5)-Pad36)") (class "Default")
      (node (ref "U3") (pin "36") (pinfunction "PL1(ICP5)_36") (pintype "bidirectional"))
    )
    (net (code "188") (name "unconnected-(U3-PL2(T5)-Pad37)") (class "Default")
      (node (ref "U3") (pin "37") (pinfunction "PL2(T5)_37") (pintype "bidirectional"))
    )
    (net (code "189") (name "unconnected-(U3-PL3(OC5A)-Pad38)") (class "Default")
      (node (ref "U3") (pin "38") (pinfunction "PL3(OC5A)_38") (pintype "bidirectional"))
    )
    (net (code "190") (name "unconnected-(U3-PL4(OC5B)-Pad39)") (class "Default")
      (node (ref "U3") (pin "39") (pinfunction "PL4(OC5B)_39") (pintype "bidirectional"))
    )
    (net (code "191") (name "unconnected-(U3-PL5(OC5C)-Pad40)") (class "Default")
      (node (ref "U3") (pin "40") (pinfunction "PL5(OC5C)_40") (pintype "bidirectional"))
    )
    (net (code "192") (name "unconnected-(U3-PL6-Pad41)") (class "Default")
      (node (ref "U3") (pin "41") (pinfunction "PL6_41") (pintype "bidirectional"))
    )
    (net (code "193") (name "unconnected-(U3-PL7-Pad42)") (class "Default")
      (node (ref "U3") (pin "42") (pinfunction "PL7_42") (pintype "bidirectional"))
    )
  )
)
